# main.net
KiCad netlist of a schematic drawn in EAGLE
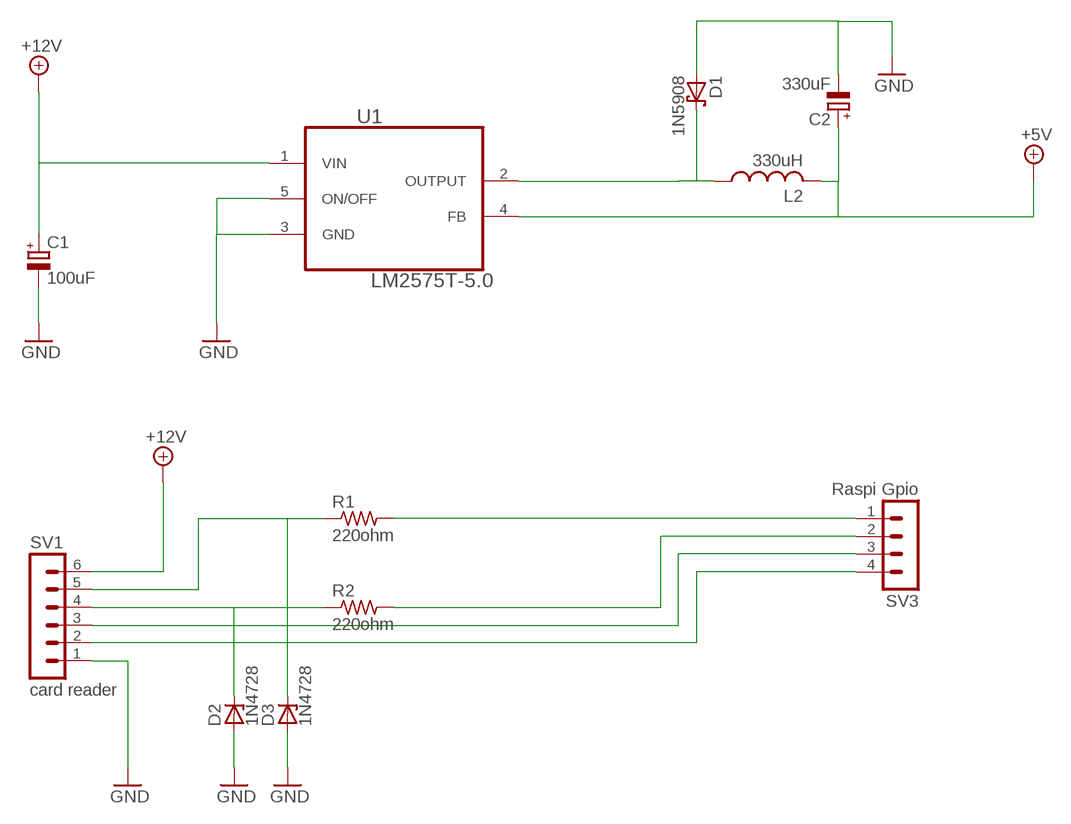
[diagram p0: schematic, sheet 1]

(export (version "E")
  (design (tool "Eeschema 10.0.6"))
  (components
    (comp (ref "C1")
      (value "100uF")
      (footprint "eagle-import:EB25D")
      (libsource (lib "eagle-import") (part "CPOL-EUE10-25"))
    )
    (comp (ref "C2")
      (value "330uF")
      (footprint "eagle-import:EB25D")
      (libsource (lib "eagle-import") (part "CPOL-EUE10-25"))
    )
    (comp (ref "D1")
      (value "1N5908")
      (footprint "eagle-import:C4111-15")
      (libsource (lib "eagle-import") (part "1N5908"))
    )
    (comp (ref "D2")
      (value "1N4728")
      (footprint "eagle-import:DO41Z10")
      (libsource (lib "eagle-import") (part "1N4728"))
    )
    (comp (ref "D3")
      (value "1N4728")
      (footprint "eagle-import:DO41Z10")
      (libsource (lib "eagle-import") (part "1N4728"))
    )
    (comp (ref "L2")
      (value "330uH")
      (footprint "eagle-import:TJ3-U2")
      (libsource (lib "eagle-import") (part "L-USTJ3-U2"))
    )
    (comp (ref "R1")
      (value "220ohm")
      (footprint "eagle-import:0204_7")
      (libsource (lib "eagle-import") (part "R-US_0204/7"))
    )
    (comp (ref "R2")
      (value "220ohm")
      (footprint "eagle-import:0204_7")
      (libsource (lib "eagle-import") (part "R-US_0204/7"))
    )
    (comp (ref "SV1")
      (value "card reader")
      (footprint "eagle-import:MA06-1")
      (libsource (lib "eagle-import") (part "MA06-1"))
    )
    (comp (ref "SV3")
      (value "Raspi Gpio")
      (footprint "eagle-import:MA04-1")
      (libsource (lib "eagle-import") (part "MA04-1"))
    )
    (comp (ref "U1")
      (value "LM2575T-5.0")
      (footprint "eagle-import:TO170P470X1016X2092-5P")
      (libsource (lib "eagle-import") (part "LM2575T-5.0"))
    )
  )
  (nets
    (net (code "1") (name "+5V") (class "Default")
      (node (ref "C2") (pin "+") (pinfunction "+_+") (pintype "passive"))
      (node (ref "L2") (pin "2") (pinfunction "2_2") (pintype "passive"))
      (node (ref "U1") (pin "4") (pinfunction "FB_4") (pintype "input"))
    )
    (net (code "2") (name "+12V") (class "Default")
      (node (ref "C1") (pin "+") (pinfunction "+_+") (pintype "passive"))
      (node (ref "SV1") (pin "6") (pinfunction "6_6") (pintype "passive"))
      (node (ref "U1") (pin "1") (pinfunction "VIN_1") (pintype "input"))
    )
    (net (code "3") (name "GND") (class "Default")
      (node (ref "C1") (pin "-") (pinfunction "-_-") (pintype "passive"))
      (node (ref "C2") (pin "-") (pinfunction "-_-") (pintype "passive"))
      (node (ref "D1") (pin "A") (pinfunction "A_A") (pintype "passive"))
      (node (ref "D2") (pin "A") (pinfunction "A_A") (pintype "passive"))
      (node (ref "D3") (pin "A") (pinfunction "A_A") (pintype "passive"))
      (node (ref "SV1") (pin "1") (pinfunction "1_1") (pintype "passive"))
      (node (ref "U1") (pin "3") (pinfunction "GND_3") (pintype "passive"))
      (node (ref "U1") (pin "5") (pinfunction "ON/OFF_5") (pintype "input"))
    )
    (net (code "4") (name "Net-(D2-PadC)") (class "Default")
      (node (ref "D2") (pin "C") (pinfunction "C_C") (pintype "passive"))
      (node (ref "R2") (pin "1") (pinfunction "1_1") (pintype "passive"))
      (node (ref "SV1") (pin "4") (pinfunction "4_4") (pintype "passive"))
    )
    (net (code "5") (name "Net-(D3-PadC)") (class "Default")
      (node (ref "D3") (pin "C") (pinfunction "C_C") (pintype "passive"))
      (node (ref "R1") (pin "1") (pinfunction "1_1") (pintype "passive"))
      (node (ref "SV1") (pin "5") (pinfunction "5_5") (pintype "passive"))
    )
    (net (code "6") (name "Net-(R1-Pad2)") (class "Default")
      (node (ref "R1") (pin "2") (pinfunction "2_2") (pintype "passive"))
      (node (ref "SV3") (pin "1") (pinfunction "1_1") (pintype "passive"))
    )
    (net (code "7") (name "Net-(R2-Pad2)") (class "Default")
      (node (ref "R2") (pin "2") (pinfunction "2_2") (pintype "passive"))
      (node (ref "SV3") (pin "2") (pinfunction "2_2") (pintype "passive"))
    )
    (net (code "8") (name "Net-(SV1-Pad2)") (class "Default")
      (node (ref "SV1") (pin "2") (pinfunction "2_2") (pintype "passive"))
      (node (ref "SV3") (pin "4") (pinfunction "4_4") (pintype "passive"))
    )
    (net (code "9") (name "Net-(SV1-Pad3)") (class "Default")
      (node (ref "SV1") (pin "3") (pinfunction "3_3") (pintype "passive"))
      (node (ref "SV3") (pin "3") (pinfunction "3_3") (pintype "passive"))
    )
    (net (code "10") (name "Net-(U1-OUTPUT)") (class "Default")
      (node (ref "D1") (pin "C") (pinfunction "C_C") (pintype "passive"))
      (node (ref "L2") (pin "1") (pinfunction "1_1") (pintype "passive"))
      (node (ref "U1") (pin "2") (pinfunction "OUTPUT_2") (pintype "output"))
    )
  )
)
